# MAR1SM.net
KiCad netlist of a schematic drawn in Altium Designer
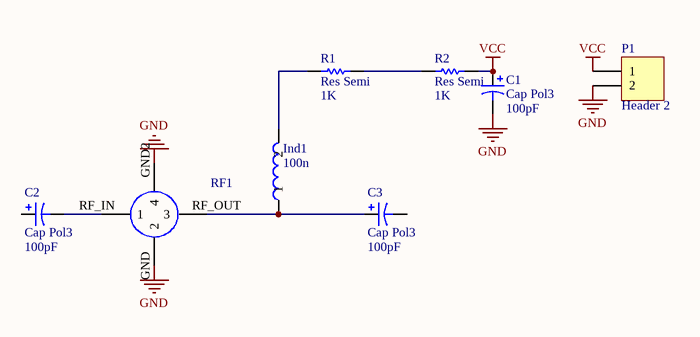
[diagram p0: MAR1SM.SchDoc]

(export (version "E")
  (design (tool "Eeschema 10.0.6"))
  (components
    (comp (ref "C1")
      (value "Cap Pol3")
      (footprint "C0805")
      (description "Polarized Capacitor (Surface Mount)")
      (fields (field (name "ALTIUM_VALUE") "100pF") (field (name "PUBLISHER") "Altium Limited"))
      (libsource (lib "Miscellaneous Devices") (part "Cap Pol3"))
    )
    (comp (ref "C2")
      (value "Cap Pol3")
      (footprint "C0805")
      (description "Polarized Capacitor (Surface Mount)")
      (fields (field (name "ALTIUM_VALUE") "100pF") (field (name "PUBLISHER") "Altium Limited"))
      (libsource (lib "Miscellaneous Devices") (part "Cap Pol3"))
    )
    (comp (ref "C3")
      (value "Cap Pol3")
      (footprint "C0805")
      (description "Polarized Capacitor (Surface Mount)")
      (fields (field (name "ALTIUM_VALUE") "100pF") (field (name "PUBLISHER") "Altium Limited"))
      (libsource (lib "Miscellaneous Devices") (part "Cap Pol3"))
    )
    (comp (ref "Ind1")
      (value "Ind2")
      (footprint "IND_7MM")
      (fields (field (name "VALOR") "100n"))
      (libsource (lib "epf") (part "Ind2"))
    )
    (comp (ref "P1")
      (value "Header 2")
      (footprint "HDR1X2")
      (description "Header, 2-Pin")
      (fields (field (name "PUBLISHER") "Altium Limited"))
      (libsource (lib "Miscellaneous Connectors") (part "Header 2"))
    )
    (comp (ref "R1")
      (value "Res Semi")
      (footprint "2012[0805]")
      (description "Semiconductor Resistor")
      (fields (field (name "ALTIUM_VALUE") "1K") (field (name "PUBLISHER") "Altium Limited"))
      (libsource (lib "Miscellaneous Devices") (part "Res Semi"))
    )
    (comp (ref "R2")
      (value "Res Semi")
      (footprint "2012[0805]")
      (description "Semiconductor Resistor")
      (fields (field (name "ALTIUM_VALUE") "1K") (field (name "PUBLISHER") "Altium Limited"))
      (libsource (lib "Miscellaneous Devices") (part "Res Semi"))
    )
    (comp (ref "RF1") (value "*") (footprint "MAR-1") (libsource (lib "epf") (part "MAR-1SM")))
  )
  (nets
    (net (code "1") (name "GND") (class "Default")
      (node (ref "C1") (pin "2") (pinfunction "2_2") (pintype "passive"))
      (node (ref "P1") (pin "2") (pinfunction "2_2") (pintype "passive"))
      (node (ref "RF1") (pin "GND") (pinfunction "2_GND") (pintype "passive"))
      (node (ref "RF1") (pin "GND2") (pinfunction "4_GND2") (pintype "passive"))
    )
    (net (code "2") (name "Net-(Ind1-Pad2)") (class "Default")
      (node (ref "Ind1") (pin "2") (pinfunction "2_2") (pintype "passive"))
      (node (ref "R1") (pin "1") (pinfunction "1_1") (pintype "passive"))
    )
    (net (code "3") (name "Net-(R1-Pad2)") (class "Default")
      (node (ref "R1") (pin "2") (pinfunction "2_2") (pintype "passive"))
      (node (ref "R2") (pin "1") (pinfunction "1_1") (pintype "passive"))
    )
    (net (code "4") (name "Net-(RF1-1)") (class "Default")
      (node (ref "C2") (pin "2") (pinfunction "2_2") (pintype "passive"))
      (node (ref "RF1") (pin "RF_IN") (pinfunction "1_RF_IN") (pintype "passive"))
    )
    (net (code "5") (name "Net-(RF1-3)") (class "Default")
      (node (ref "C3") (pin "1") (pinfunction "1_1") (pintype "passive"))
      (node (ref "Ind1") (pin "1") (pinfunction "1_1") (pintype "passive"))
      (node (ref "RF1") (pin "RF_OUT") (pinfunction "3_RF_OUT") (pintype "passive"))
    )
    (net (code "6") (name "VCC") (class "Default")
      (node (ref "C1") (pin "1") (pinfunction "1_1") (pintype "passive"))
      (node (ref "P1") (pin "1") (pinfunction "1_1") (pintype "passive"))
      (node (ref "R2") (pin "2") (pinfunction "2_2") (pintype "passive"))
    )
    (net (code "7") (name "unconnected-(C2-Pad1)") (class "Default")
      (node (ref "C2") (pin "1") (pinfunction "1_1") (pintype "passive"))
    )
    (net (code "8") (name "unconnected-(C3-Pad2)") (class "Default")
      (node (ref "C3") (pin "2") (pinfunction "2_2") (pintype "passive"))
    )
  )
)
